# LGA-14_3x2_5.net
KiCad netlist of a schematic drawn in EAGLE
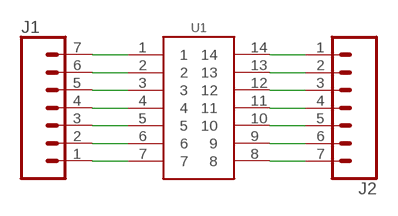
[diagram p0: schematic, sheet 1]

(export (version "E")
  (design (tool "Eeschema 10.0.6"))
  (components
    (comp (ref "J1")
      (value "CONN_07")
      (footprint "eagle-import:1X07")
      (libsource (lib "eagle-import") (part "CONN_07"))
    )
    (comp (ref "J2")
      (value "CONN_07")
      (footprint "eagle-import:1X07")
      (libsource (lib "eagle-import") (part "CONN_07"))
    )
    (comp (ref "U1")
      (value "GEN_14LGA_3X2.5")
      (footprint "eagle-import:PQFN50P250X300X97-14N")
      (libsource (lib "eagle-import") (part "GEN_14LGA_3X2.5"))
    )
  )
  (nets
    (net (code "1") (name "Net-(J1-Pad1)") (class "Default")
      (node (ref "J1") (pin "1") (pinfunction "1_1") (pintype "passive"))
      (node (ref "U1") (pin "7") (pinfunction "7_7") (pintype "bidirectional"))
    )
    (net (code "2") (name "Net-(J1-Pad2)") (class "Default")
      (node (ref "J1") (pin "2") (pinfunction "2_2") (pintype "passive"))
      (node (ref "U1") (pin "6") (pinfunction "6_6") (pintype "bidirectional"))
    )
    (net (code "3") (name "Net-(J1-Pad3)") (class "Default")
      (node (ref "J1") (pin "3") (pinfunction "3_3") (pintype "passive"))
      (node (ref "U1") (pin "5") (pinfunction "5_5") (pintype "bidirectional"))
    )
    (net (code "4") (name "Net-(J1-Pad4)") (class "Default")
      (node (ref "J1") (pin "4") (pinfunction "4_4") (pintype "passive"))
      (node (ref "U1") (pin "4") (pinfunction "4_4") (pintype "bidirectional"))
    )
    (net (code "5") (name "Net-(J1-Pad5)") (class "Default")
      (node (ref "J1") (pin "5") (pinfunction "5_5") (pintype "passive"))
      (node (ref "U1") (pin "3") (pinfunction "3_3") (pintype "bidirectional"))
    )
    (net (code "6") (name "Net-(J1-Pad6)") (class "Default")
      (node (ref "J1") (pin "6") (pinfunction "6_6") (pintype "passive"))
      (node (ref "U1") (pin "2") (pinfunction "2_2") (pintype "bidirectional"))
    )
    (net (code "7") (name "Net-(J1-Pad7)") (class "Default")
      (node (ref "J1") (pin "7") (pinfunction "7_7") (pintype "passive"))
      (node (ref "U1") (pin "1") (pinfunction "1_1") (pintype "bidirectional"))
    )
    (net (code "8") (name "Net-(J2-Pad1)") (class "Default")
      (node (ref "J2") (pin "1") (pinfunction "1_1") (pintype "passive"))
      (node (ref "U1") (pin "14") (pinfunction "14_14") (pintype "bidirectional"))
    )
    (net (code "9") (name "Net-(J2-Pad2)") (class "Default")
      (node (ref "J2") (pin "2") (pinfunction "2_2") (pintype "passive"))
      (node (ref "U1") (pin "13") (pinfunction "13_13") (pintype "bidirectional"))
    )
    (net (code "10") (name "Net-(J2-Pad3)") (class "Default")
      (node (ref "J2") (pin "3") (pinfunction "3_3") (pintype "passive"))
      (node (ref "U1") (pin "12") (pinfunction "12_12") (pintype "bidirectional"))
    )
    (net (code "11") (name "Net-(J2-Pad4)") (class "Default")
      (node (ref "J2") (pin "4") (pinfunction "4_4") (pintype "passive"))
      (node (ref "U1") (pin "11") (pinfunction "11_11") (pintype "bidirectional"))
    )
    (net (code "12") (name "Net-(J2-Pad5)") (class "Default")
      (node (ref "J2") (pin "5") (pinfunction "5_5") (pintype "passive"))
      (node (ref "U1") (pin "10") (pinfunction "10_10") (pintype "bidirectional"))
    )
    (net (code "13") (name "Net-(J2-Pad6)") (class "Default")
      (node (ref "J2") (pin "6") (pinfunction "6_6") (pintype "passive"))
      (node (ref "U1") (pin "9") (pinfunction "9_9") (pintype "bidirectional"))
    )
    (net (code "14") (name "Net-(J2-Pad7)") (class "Default")
      (node (ref "J2") (pin "7") (pinfunction "7_7") (pintype "passive"))
      (node (ref "U1") (pin "8") (pinfunction "8_8") (pintype "bidirectional"))
    )
  )
)
